# H_Bridge.net
KiCad netlist of a schematic drawn in Altium Designer
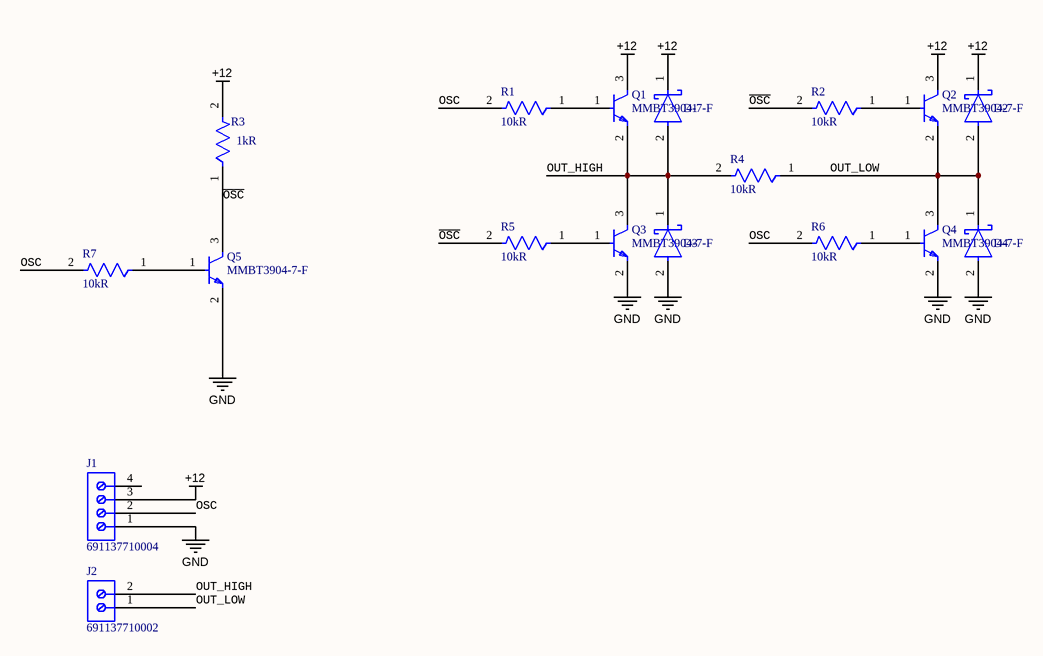
[diagram p0: H Bridge.SchDoc]

(export (version "E")
  (design (tool "Eeschema 10.0.6"))
  (components
    (comp (ref "D1")
      (value "SK520B")
      (footprint "FP-SMB-MFG")
      (description "SK520B Diode Schottky 200V 5A Smb")
      (libsource (lib "Altium Content Vault") (part "c1678fac7984e62e0809fbf79c06691"))
    )
    (comp (ref "D2")
      (value "SK520B")
      (footprint "FP-SMB-MFG")
      (description "SK520B Diode Schottky 200V 5A Smb")
      (libsource (lib "Altium Content Vault") (part "c1678fac7984e62e0809fbf79c06691"))
    )
    (comp (ref "D3")
      (value "SK520B")
      (footprint "FP-SMB-MFG")
      (description "SK520B Diode Schottky 200V 5A Smb")
      (libsource (lib "Altium Content Vault") (part "c1678fac7984e62e0809fbf79c06691"))
    )
    (comp (ref "D4")
      (value "SK520B")
      (footprint "FP-SMB-MFG")
      (description "SK520B Diode Schottky 200V 5A Smb")
      (libsource (lib "Altium Content Vault") (part "c1678fac7984e62e0809fbf79c06691"))
    )
    (comp (ref "J1")
      (value "691137710004")
      (footprint "691137710004")
      (libsource (lib "Altium Content Vault") (part "TBL - 1R - 04P - Screw"))
    )
    (comp (ref "J2")
      (value "691137710002")
      (footprint "691137710002")
      (libsource (lib "Altium Content Vault") (part "TBL - 1R - 02P - Screw"))
    )
    (comp (ref "Q1")
      (value "MMBT3904-7-F")
      (footprint "FP-SOT23-IPC_A")
      (description "TRANS NPN 40V 0.2A SMD SOT23-3")
      (libsource (lib "Altium Content Vault") (part "b44e953556f554d0102664c7d152cb4"))
    )
    (comp (ref "Q2")
      (value "MMBT3904-7-F")
      (footprint "FP-SOT23-IPC_A")
      (description "TRANS NPN 40V 0.2A SMD SOT23-3")
      (libsource (lib "Altium Content Vault") (part "b44e953556f554d0102664c7d152cb4"))
    )
    (comp (ref "Q3")
      (value "MMBT3904-7-F")
      (footprint "FP-SOT23-IPC_A")
      (description "TRANS NPN 40V 0.2A SMD SOT23-3")
      (libsource (lib "Altium Content Vault") (part "b44e953556f554d0102664c7d152cb4"))
    )
    (comp (ref "Q4")
      (value "MMBT3904-7-F")
      (footprint "FP-SOT23-IPC_A")
      (description "TRANS NPN 40V 0.2A SMD SOT23-3")
      (libsource (lib "Altium Content Vault") (part "b44e953556f554d0102664c7d152cb4"))
    )
    (comp (ref "Q5")
      (value "MMBT3904-7-F")
      (footprint "FP-SOT23-IPC_A")
      (description "TRANS NPN 40V 0.2A SMD SOT23-3")
      (libsource (lib "Altium Content Vault") (part "b44e953556f554d0102664c7d152cb4"))
    )
    (comp (ref "R1")
      (value "RR1220P-103-D")
      (footprint "FP-RR1220-IPC_A")
      (description "10kΩ ±0.5% 0.1W 1/10W Chip Resistor 0805 (2012 Metric) Thin Film")
      (fields (field (name "RESISTANCE") "10kR") (field (name "TOLERANCE") "0.5%"))
      (libsource (lib "Altium Content Vault") (part "1029c3af85768c4190bb7ad29bc67b5"))
    )
    (comp (ref "R2")
      (value "RR1220P-103-D")
      (footprint "FP-RR1220-IPC_A")
      (description "10kΩ ±0.5% 0.1W 1/10W Chip Resistor 0805 (2012 Metric) Thin Film")
      (fields (field (name "RESISTANCE") "10kR") (field (name "TOLERANCE") "0.5%"))
      (libsource (lib "Altium Content Vault") (part "1029c3af85768c4190bb7ad29bc67b5"))
    )
    (comp (ref "R3")
      (value "RR1220P-102-D")
      (footprint "FP-RR1220-IPC_A")
      (description "1kΩ ±0.5% 0.1W 1/10W Chip Resistor 0805 (2012 Metric) Thin Film")
      (fields (field (name "TOLERANCE") "0.5%") (field (name "RESISTANCE") "1kR"))
      (libsource (lib "Altium Content Vault") (part "1029c3af85768c4190bb7ad29bc67b5"))
    )
    (comp (ref "R4")
      (value "RR1220P-103-D")
      (footprint "FP-RR1220-IPC_A")
      (description "10kΩ ±0.5% 0.1W 1/10W Chip Resistor 0805 (2012 Metric) Thin Film")
      (fields (field (name "RESISTANCE") "10kR") (field (name "TOLERANCE") "0.5%"))
      (libsource (lib "Altium Content Vault") (part "1029c3af85768c4190bb7ad29bc67b5"))
    )
    (comp (ref "R5")
      (value "RR1220P-103-D")
      (footprint "FP-RR1220-IPC_A")
      (description "10kΩ ±0.5% 0.1W 1/10W Chip Resistor 0805 (2012 Metric) Thin Film")
      (fields (field (name "RESISTANCE") "10kR") (field (name "TOLERANCE") "0.5%"))
      (libsource (lib "Altium Content Vault") (part "1029c3af85768c4190bb7ad29bc67b5"))
    )
    (comp (ref "R6")
      (value "RR1220P-103-D")
      (footprint "FP-RR1220-IPC_A")
      (description "10kΩ ±0.5% 0.1W 1/10W Chip Resistor 0805 (2012 Metric) Thin Film")
      (fields (field (name "RESISTANCE") "10kR") (field (name "TOLERANCE") "0.5%"))
      (libsource (lib "Altium Content Vault") (part "1029c3af85768c4190bb7ad29bc67b5"))
    )
    (comp (ref "R7")
      (value "RR1220P-103-D")
      (footprint "FP-RR1220-IPC_A")
      (description "10kΩ ±0.5% 0.1W 1/10W Chip Resistor 0805 (2012 Metric) Thin Film")
      (fields (field (name "RESISTANCE") "10kR") (field (name "TOLERANCE") "0.5%"))
      (libsource (lib "Altium Content Vault") (part "1029c3af85768c4190bb7ad29bc67b5"))
    )
  )
  (nets
    (net (code "1") (name "+12") (class "Default")
      (node (ref "D1") (pin "1") (pinfunction "C_1") (pintype "passive"))
      (node (ref "D2") (pin "1") (pinfunction "C_1") (pintype "passive"))
      (node (ref "J1") (pin "3") (pinfunction "3_3") (pintype "passive"))
      (node (ref "Q1") (pin "3") (pinfunction "C_3") (pintype "passive"))
      (node (ref "Q2") (pin "3") (pinfunction "C_3") (pintype "passive"))
      (node (ref "R3") (pin "2") (pinfunction "2_2") (pintype "passive"))
    )
    (net (code "2") (name "/OSC") (class "Default")
      (node (ref "J1") (pin "2") (pinfunction "2_2") (pintype "passive"))
      (node (ref "R1") (pin "2") (pinfunction "2_2") (pintype "passive"))
      (node (ref "R6") (pin "2") (pinfunction "2_2") (pintype "passive"))
      (node (ref "R7") (pin "2") (pinfunction "2_2") (pintype "passive"))
    )
    (net (code "3") (name "/OUT_HIGH") (class "Default")
      (node (ref "D1") (pin "2") (pinfunction "A_2") (pintype "passive"))
      (node (ref "D3") (pin "1") (pinfunction "C_1") (pintype "passive"))
      (node (ref "J2") (pin "2") (pinfunction "2_2") (pintype "passive"))
      (node (ref "Q1") (pin "2") (pinfunction "E_2") (pintype "passive"))
      (node (ref "Q3") (pin "3") (pinfunction "C_3") (pintype "passive"))
      (node (ref "R4") (pin "2") (pinfunction "2_2") (pintype "passive"))
    )
    (net (code "4") (name "/OUT_LOW") (class "Default")
      (node (ref "D2") (pin "2") (pinfunction "A_2") (pintype "passive"))
      (node (ref "D4") (pin "1") (pinfunction "C_1") (pintype "passive"))
      (node (ref "J2") (pin "1") (pinfunction "1_1") (pintype "passive"))
      (node (ref "Q2") (pin "2") (pinfunction "E_2") (pintype "passive"))
      (node (ref "Q4") (pin "3") (pinfunction "C_3") (pintype "passive"))
      (node (ref "R4") (pin "1") (pinfunction "1_1") (pintype "passive"))
    )
    (net (code "5") (name "/~{OSC}") (class "Default")
      (node (ref "Q5") (pin "3") (pinfunction "C_3") (pintype "passive"))
      (node (ref "R2") (pin "2") (pinfunction "2_2") (pintype "passive"))
      (node (ref "R3") (pin "1") (pinfunction "1_1") (pintype "passive"))
      (node (ref "R5") (pin "2") (pinfunction "2_2") (pintype "passive"))
    )
    (net (code "6") (name "GND") (class "Default")
      (node (ref "D3") (pin "2") (pinfunction "A_2") (pintype "passive"))
      (node (ref "D4") (pin "2") (pinfunction "A_2") (pintype "passive"))
      (node (ref "J1") (pin "1") (pinfunction "1_1") (pintype "passive"))
      (node (ref "Q3") (pin "2") (pinfunction "E_2") (pintype "passive"))
      (node (ref "Q4") (pin "2") (pinfunction "E_2") (pintype "passive"))
      (node (ref "Q5") (pin "2") (pinfunction "E_2") (pintype "passive"))
    )
    (net (code "7") (name "Net-(Q1-B)") (class "Default")
      (node (ref "Q1") (pin "1") (pinfunction "B_1") (pintype "passive"))
      (node (ref "R1") (pin "1") (pinfunction "1_1") (pintype "passive"))
    )
    (net (code "8") (name "Net-(Q2-B)") (class "Default")
      (node (ref "Q2") (pin "1") (pinfunction "B_1") (pintype "passive"))
      (node (ref "R2") (pin "1") (pinfunction "1_1") (pintype "passive"))
    )
    (net (code "9") (name "Net-(Q3-B)") (class "Default")
      (node (ref "Q3") (pin "1") (pinfunction "B_1") (pintype "passive"))
      (node (ref "R5") (pin "1") (pinfunction "1_1") (pintype "passive"))
    )
    (net (code "10") (name "Net-(Q4-B)") (class "Default")
      (node (ref "Q4") (pin "1") (pinfunction "B_1") (pintype "passive"))
      (node (ref "R6") (pin "1") (pinfunction "1_1") (pintype "passive"))
    )
    (net (code "11") (name "Net-(Q5-B)") (class "Default")
      (node (ref "Q5") (pin "1") (pinfunction "B_1") (pintype "passive"))
      (node (ref "R7") (pin "1") (pinfunction "1_1") (pintype "passive"))
    )
    (net (code "12") (name "unconnected-(J1-Pad4)") (class "Default")
      (node (ref "J1") (pin "4") (pinfunction "4_4") (pintype "passive"))
    )
  )
)
